# schematic.net
KiCad netlist of a schematic drawn in EasyEDA
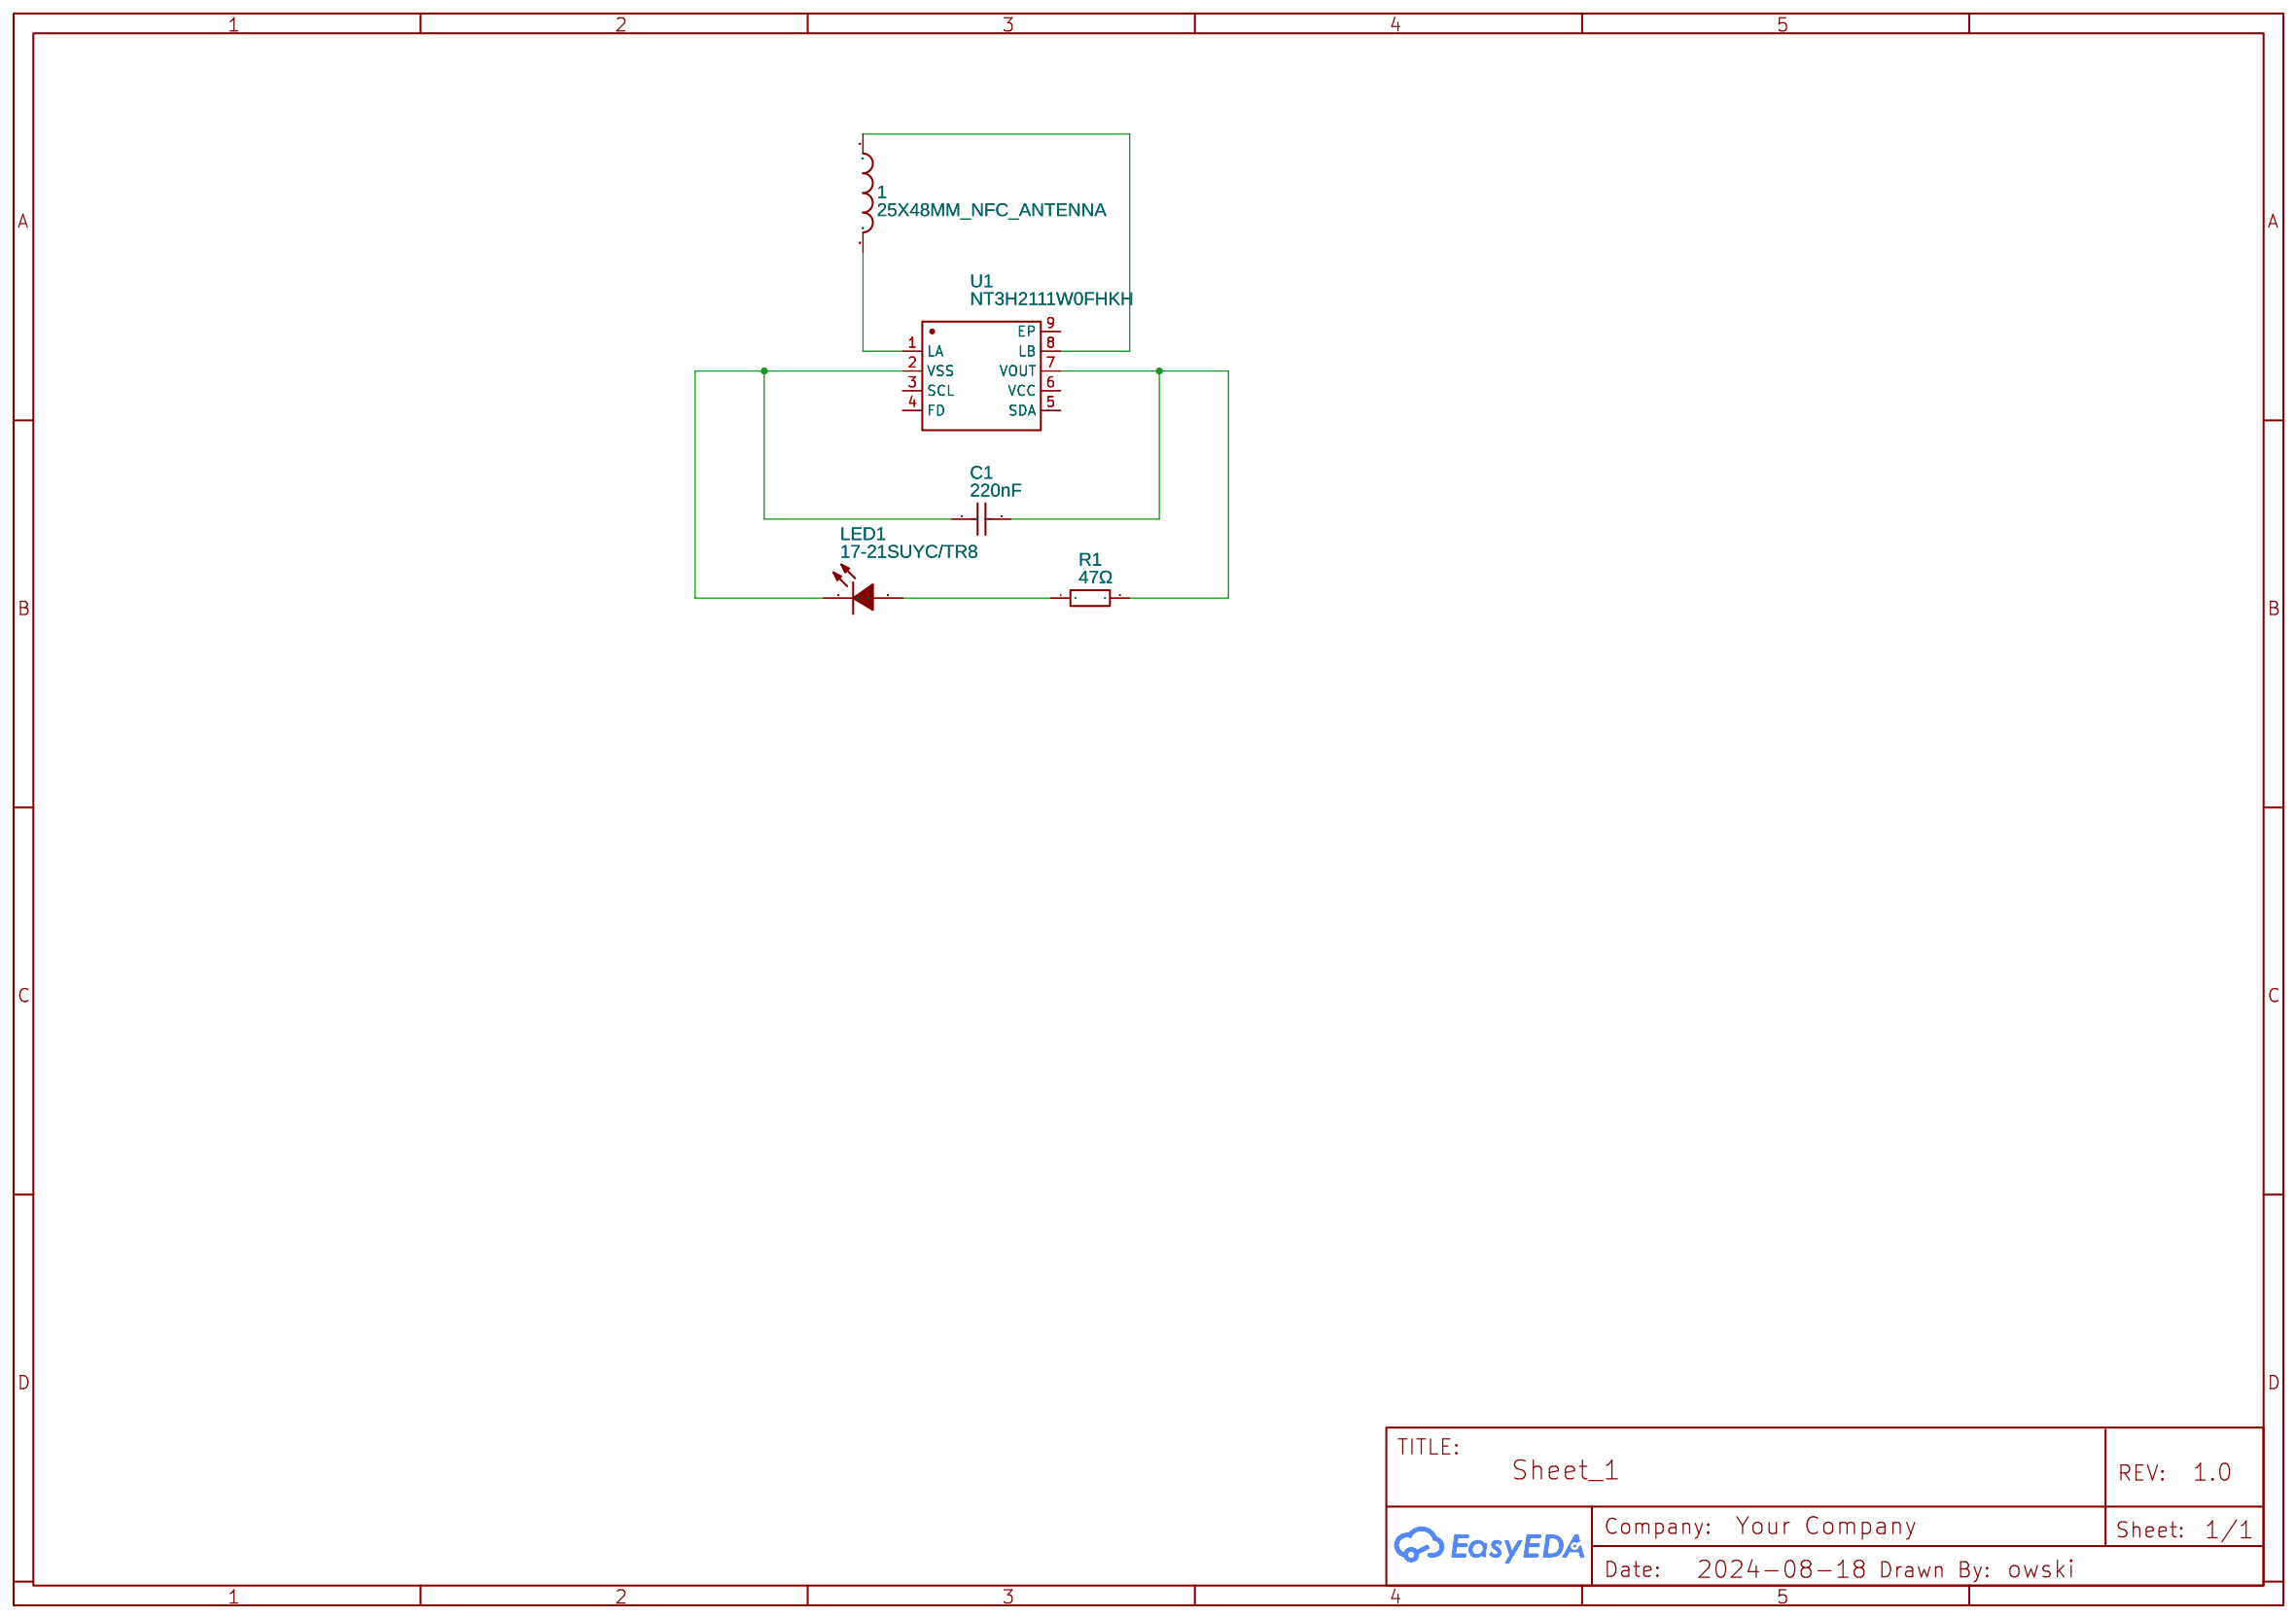
[diagram p0: Sheet_1]
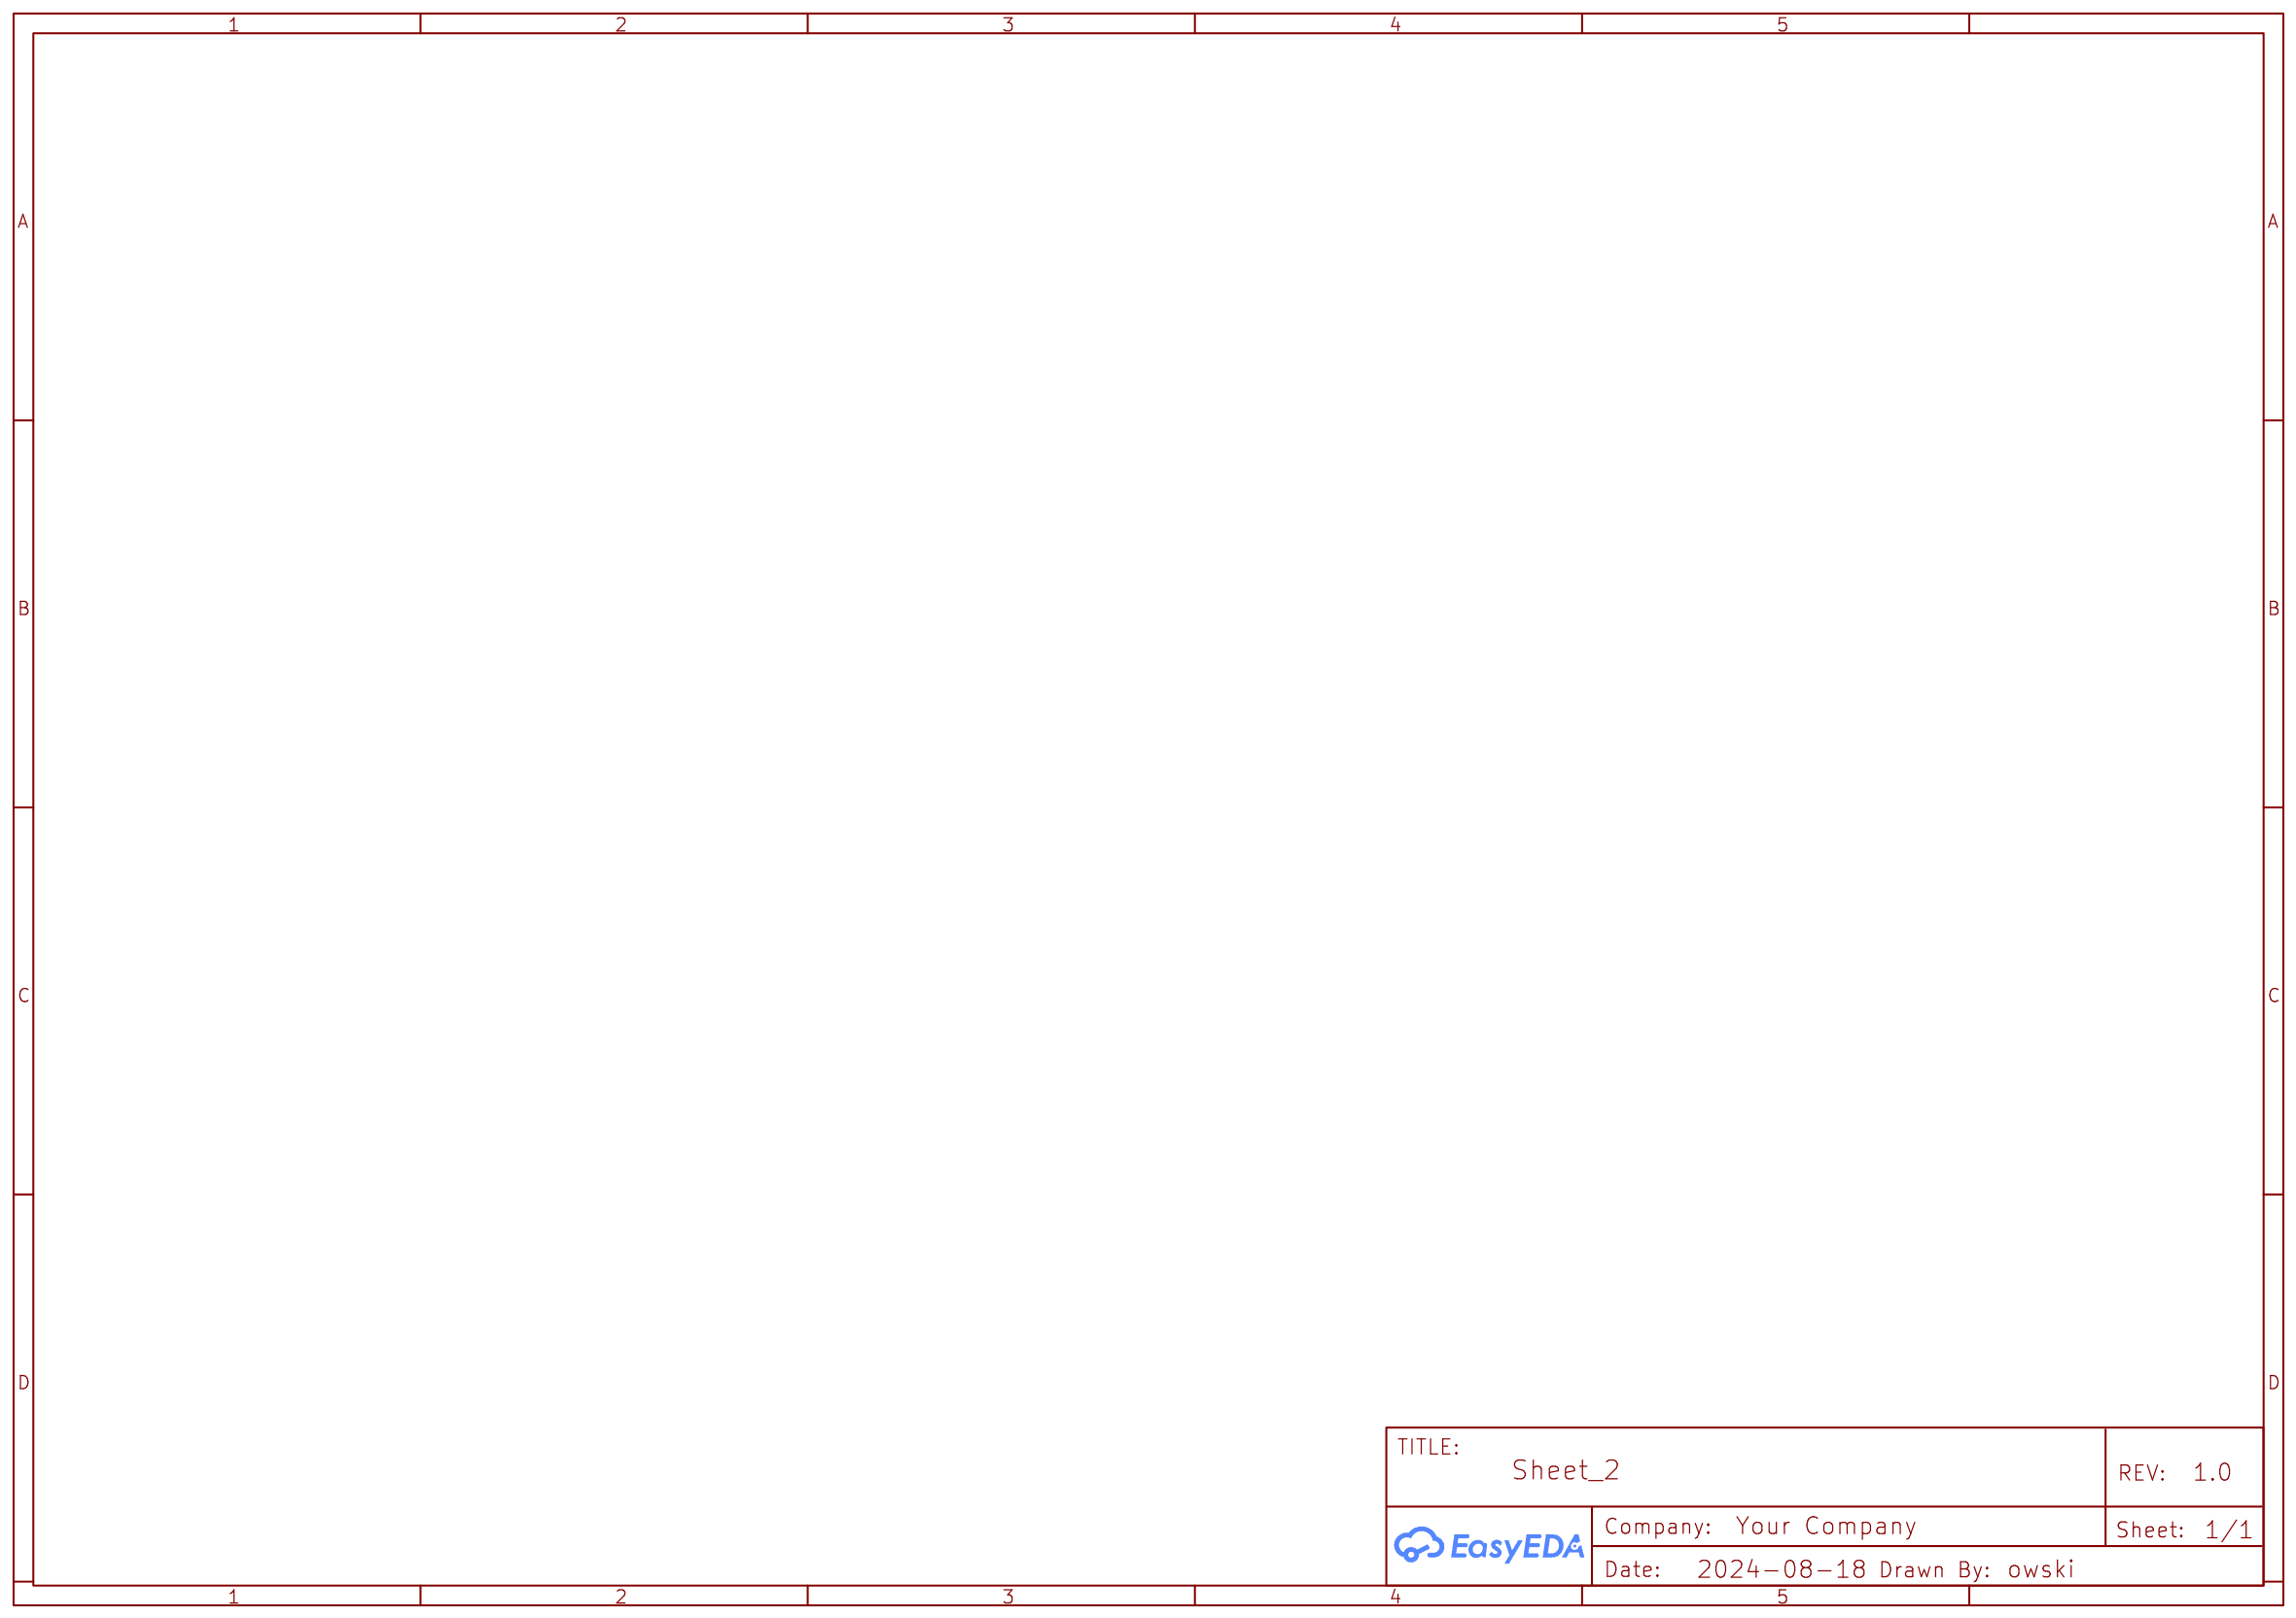
[diagram p1: Sheet_2]

(export (version "E")
  (design (tool "Eeschema 10.0.6"))
  (components
    (comp (ref "1") (value "25X48MM_NFC_ANTENNA") (libsource (lib "") (part "25X48MM_NFC_ANTENNA")))
    (comp (ref "C1")
      (value "220nF")
      (fields
        (field (name "Manufacturer Part") "CL10B224KA8NNNC")
        (field (name "Manufacturer") "SAMSUNG(三星)")
      )
      (libsource (lib "") (part "CL10B224KA8NNNC"))
    )
    (comp (ref "LED1")
      (value "17-21SUYC/TR8")
      (fields (field (name "Manufacturer Part") "KT-0805黄灯") (field (name "Manufacturer") "KENTO"))
      (libsource (lib "") (part "17-21SUYC/TR8"))
    )
    (comp (ref "R1")
      (value "47Ω")
      (fields
        (field (name "Manufacturer Part") "0603WAF470JT5E")
        (field (name "Manufacturer") "UNI-ROYAL(厚声)")
      )
      (libsource (lib "") (part "0603WAF470JT5E"))
    )
    (comp (ref "U1")
      (value "NT3H2111W0FHKH")
      (fields (field (name "Manufacturer") "NXP(恩智浦)"))
      (libsource (lib "") (part "NT3H2111W0FHKH"))
    )
  )
  (nets
    (net (code "1") (name "Net-(LED1-+)") (class "Default")
      (node (ref "LED1") (pin "1") (pinfunction "+_1") (pintype "unspecified"))
      (node (ref "R1") (pin "1") (pinfunction "1_1") (pintype "input"))
    )
    (net (code "2") (name "Net-(LED1--)") (class "Default")
      (node (ref "C1") (pin "1") (pinfunction "1_1") (pintype "input"))
      (node (ref "LED1") (pin "2") (pinfunction "-_2") (pintype "unspecified"))
      (node (ref "U1") (pin "2") (pinfunction "VSS_2") (pintype "unspecified"))
    )
    (net (code "3") (name "Net-(U1-LA)") (class "Default")
      (node (ref "1") (pin "P$2") (pinfunction "P$2_P$2") (pintype "bidirectional"))
      (node (ref "U1") (pin "1") (pinfunction "LA_1") (pintype "unspecified"))
    )
    (net (code "4") (name "Net-(U1-LB)") (class "Default")
      (node (ref "1") (pin "P$1") (pinfunction "P$1_P$1") (pintype "bidirectional"))
      (node (ref "U1") (pin "8") (pinfunction "LB_8") (pintype "unspecified"))
    )
    (net (code "5") (name "Net-(U1-VOUT)") (class "Default")
      (node (ref "C1") (pin "2") (pinfunction "2_2") (pintype "input"))
      (node (ref "R1") (pin "2") (pinfunction "2_2") (pintype "input"))
      (node (ref "U1") (pin "7") (pinfunction "VOUT_7") (pintype "unspecified"))
    )
    (net (code "6") (name "unconnected-(U1-EP-Pad9)") (class "Default")
      (node (ref "U1") (pin "9") (pinfunction "EP_9") (pintype "unspecified"))
    )
    (net (code "7") (name "unconnected-(U1-FD-Pad4)") (class "Default")
      (node (ref "U1") (pin "4") (pinfunction "FD_4") (pintype "unspecified"))
    )
    (net (code "8") (name "unconnected-(U1-SCL-Pad3)") (class "Default")
      (node (ref "U1") (pin "3") (pinfunction "SCL_3") (pintype "unspecified"))
    )
    (net (code "9") (name "unconnected-(U1-SDA-Pad5)") (class "Default")
      (node (ref "U1") (pin "5") (pinfunction "SDA_5") (pintype "unspecified"))
    )
    (net (code "10") (name "unconnected-(U1-VCC-Pad6)") (class "Default")
      (node (ref "U1") (pin "6") (pinfunction "VCC_6") (pintype "unspecified"))
    )
  )
)
